# QTPyNoisyBoi.net
KiCad netlist of a schematic drawn in EAGLE
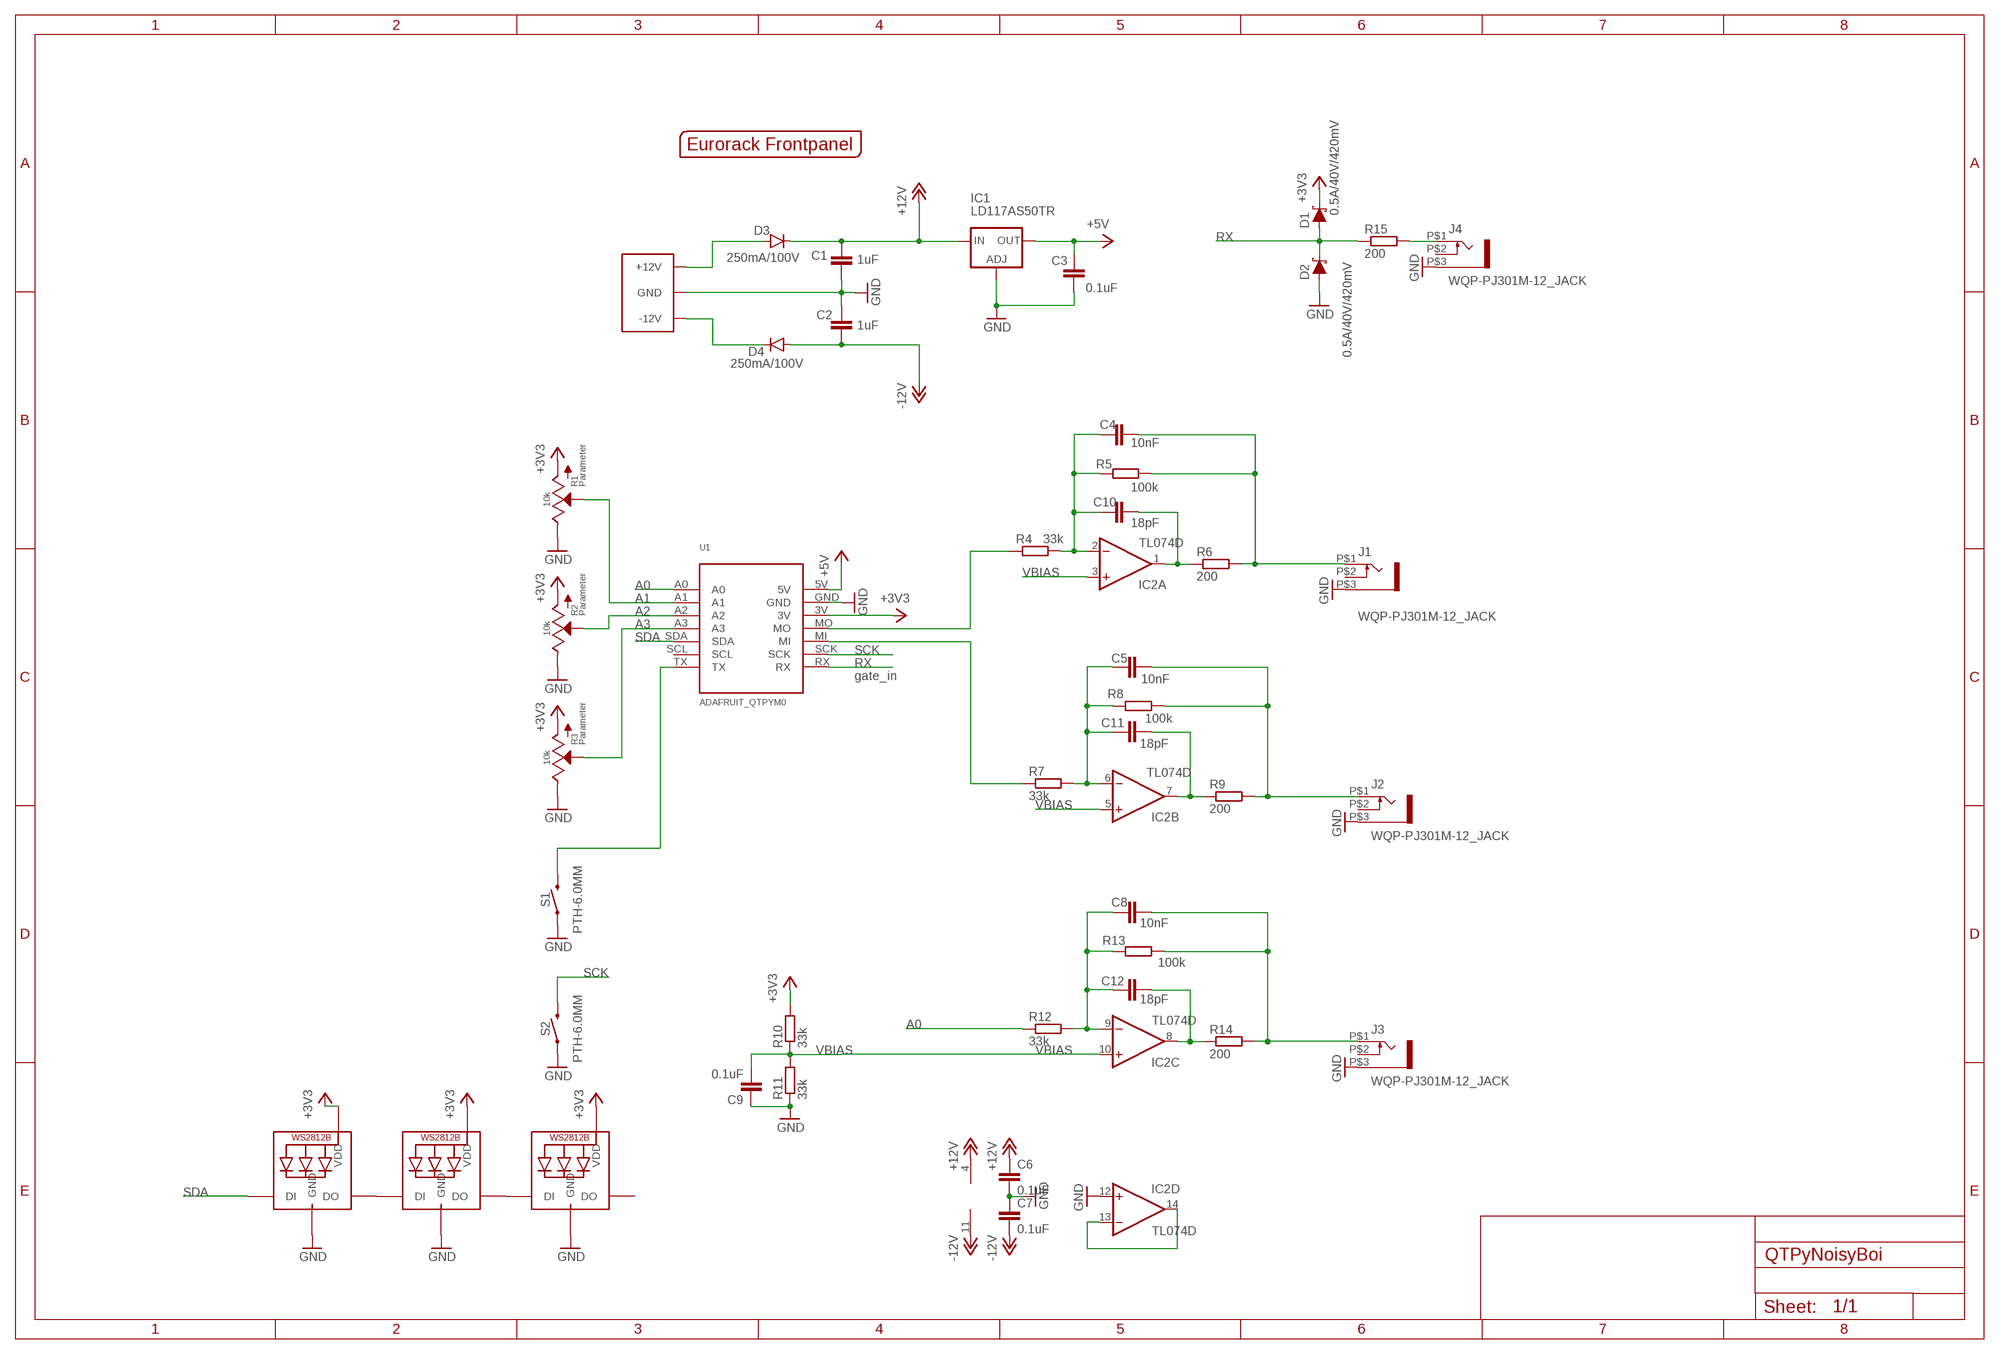
[diagram p0: schematic, sheet 1]

(export (version "E")
  (design (tool "Eeschema 10.0.6"))
  (components
    (comp (ref "C1")
      (value "1uF")
      (footprint "eagle-import:C0805")
      (libsource (lib "eagle-import") (part "C-EUC0805"))
    )
    (comp (ref "C2")
      (value "1uF")
      (footprint "eagle-import:C0805")
      (libsource (lib "eagle-import") (part "C-EUC0805"))
    )
    (comp (ref "C3")
      (value "0.1uF")
      (footprint "eagle-import:C0805")
      (libsource (lib "eagle-import") (part "C-EUC0805"))
    )
    (comp (ref "C4")
      (value "10nF")
      (footprint "eagle-import:C0805")
      (libsource (lib "eagle-import") (part "C-EUC0805"))
    )
    (comp (ref "C5")
      (value "10nF")
      (footprint "eagle-import:C0805")
      (libsource (lib "eagle-import") (part "C-EUC0805"))
    )
    (comp (ref "C6")
      (value "0.1uF")
      (footprint "eagle-import:C0805")
      (libsource (lib "eagle-import") (part "C-EUC0805"))
    )
    (comp (ref "C7")
      (value "0.1uF")
      (footprint "eagle-import:C0805")
      (libsource (lib "eagle-import") (part "C-EUC0805"))
    )
    (comp (ref "C8")
      (value "10nF")
      (footprint "eagle-import:C0805")
      (libsource (lib "eagle-import") (part "C-EUC0805"))
    )
    (comp (ref "C9")
      (value "0.1uF")
      (footprint "eagle-import:C0805")
      (libsource (lib "eagle-import") (part "C-EUC0805"))
    )
    (comp (ref "C10")
      (value "18pF")
      (footprint "eagle-import:C0805")
      (libsource (lib "eagle-import") (part "C-EUC0805"))
    )
    (comp (ref "C11")
      (value "18pF")
      (footprint "eagle-import:C0805")
      (libsource (lib "eagle-import") (part "C-EUC0805"))
    )
    (comp (ref "C12")
      (value "18pF")
      (footprint "eagle-import:C0805")
      (libsource (lib "eagle-import") (part "C-EUC0805"))
    )
    (comp (ref "D1")
      (value "0.5A/40V/420mV")
      (footprint "eagle-import:SOD-323")
      (libsource (lib "eagle-import") (part "DIODE-SCHOTTKY-PMEG4005EJ"))
    )
    (comp (ref "D2")
      (value "0.5A/40V/420mV")
      (footprint "eagle-import:SOD-323")
      (libsource (lib "eagle-import") (part "DIODE-SCHOTTKY-PMEG4005EJ"))
    )
    (comp (ref "D3")
      (value "250mA/100V")
      (footprint "eagle-import:SOD-323")
      (libsource (lib "eagle-import") (part "DIODEBAS16"))
    )
    (comp (ref "D4")
      (value "250mA/100V")
      (footprint "eagle-import:SOD-323")
      (libsource (lib "eagle-import") (part "DIODEBAS16"))
    )
    (comp (ref "DIM1")
      (value "EURO_POWER_LOCKSKINNY")
      (footprint "eagle-import:EURO_POWER_HEADER")
      (libsource (lib "eagle-import") (part "EURO_POWER_LOCKSKINNY"))
    )
    (comp (ref "IC1")
      (value "LD117AS50TR")
      (footprint "eagle-import:SOT223")
      (libsource (lib "eagle-import") (part "LD117A?S50TR"))
    )
    (comp (ref "IC2")
      (value "TL074D")
      (footprint "eagle-import:SO14")
      (libsource (lib "eagle-import") (part "TL074D"))
    )
    (comp (ref "J1")
      (value "WQP-PJ301M-12_JACK")
      (footprint "eagle-import:WQP-PJ301M-12_JACK")
      (libsource (lib "eagle-import") (part "WQP-PJ301M-12_JACK"))
    )
    (comp (ref "J2")
      (value "WQP-PJ301M-12_JACK")
      (footprint "eagle-import:WQP-PJ301M-12_JACK")
      (libsource (lib "eagle-import") (part "WQP-PJ301M-12_JACK"))
    )
    (comp (ref "J3")
      (value "WQP-PJ301M-12_JACK")
      (footprint "eagle-import:WQP-PJ301M-12_JACK")
      (libsource (lib "eagle-import") (part "WQP-PJ301M-12_JACK"))
    )
    (comp (ref "J4")
      (value "WQP-PJ301M-12_JACK")
      (footprint "eagle-import:WQP-PJ301M-12_JACK")
      (libsource (lib "eagle-import") (part "WQP-PJ301M-12_JACK"))
    )
    (comp (ref "LED1")
      (value "WS2812B5050")
      (footprint "eagle-import:WS2812B")
      (libsource (lib "eagle-import") (part "WS2812B5050"))
    )
    (comp (ref "LED2")
      (value "WS2812B5050")
      (footprint "eagle-import:WS2812B")
      (libsource (lib "eagle-import") (part "WS2812B5050"))
    )
    (comp (ref "LED3")
      (value "WS2812B5050")
      (footprint "eagle-import:WS2812B")
      (libsource (lib "eagle-import") (part "WS2812B5050"))
    )
    (comp (ref "R1")
      (value "10k")
      (footprint "eagle-import:OG-POTS_ALPS_POT_VERTICAL")
      (fields (field (name "DESC") "Parameter"))
      (libsource (lib "eagle-import") (part "POTZEPHPOT"))
    )
    (comp (ref "R2")
      (value "10k")
      (footprint "eagle-import:OG-POTS_ALPS_POT_VERTICAL")
      (fields (field (name "DESC") "Parameter"))
      (libsource (lib "eagle-import") (part "POTZEPHPOT"))
    )
    (comp (ref "R3")
      (value "10k")
      (footprint "eagle-import:OG-POTS_ALPS_POT_VERTICAL")
      (fields (field (name "DESC") "Parameter"))
      (libsource (lib "eagle-import") (part "POTZEPHPOT"))
    )
    (comp (ref "R4")
      (value "33k")
      (footprint "eagle-import:R0805")
      (libsource (lib "eagle-import") (part "R-EU_R0805"))
    )
    (comp (ref "R5")
      (value "100k")
      (footprint "eagle-import:R0805")
      (libsource (lib "eagle-import") (part "R-EU_R0805"))
    )
    (comp (ref "R6")
      (value "200")
      (footprint "eagle-import:R0805")
      (libsource (lib "eagle-import") (part "R-EU_R0805"))
    )
    (comp (ref "R7")
      (value "33k")
      (footprint "eagle-import:R0805")
      (libsource (lib "eagle-import") (part "R-EU_R0805"))
    )
    (comp (ref "R8")
      (value "100k")
      (footprint "eagle-import:R0805")
      (libsource (lib "eagle-import") (part "R-EU_R0805"))
    )
    (comp (ref "R9")
      (value "200")
      (footprint "eagle-import:R0805")
      (libsource (lib "eagle-import") (part "R-EU_R0805"))
    )
    (comp (ref "R10")
      (value "33k")
      (footprint "eagle-import:R0805")
      (libsource (lib "eagle-import") (part "R-EU_R0805"))
    )
    (comp (ref "R11")
      (value "33k")
      (footprint "eagle-import:R0805")
      (libsource (lib "eagle-import") (part "R-EU_R0805"))
    )
    (comp (ref "R12")
      (value "33k")
      (footprint "eagle-import:R0805")
      (libsource (lib "eagle-import") (part "R-EU_R0805"))
    )
    (comp (ref "R13")
      (value "100k")
      (footprint "eagle-import:R0805")
      (libsource (lib "eagle-import") (part "R-EU_R0805"))
    )
    (comp (ref "R14")
      (value "200")
      (footprint "eagle-import:R0805")
      (libsource (lib "eagle-import") (part "R-EU_R0805"))
    )
    (comp (ref "R15")
      (value "200")
      (footprint "eagle-import:R0805")
      (libsource (lib "eagle-import") (part "R-EU_R0805"))
    )
    (comp (ref "S1")
      (value "PTH-6.0MM")
      (footprint "eagle-import:TACTILE_SWITCH_PTH_6.0MM")
      (libsource (lib "eagle-import") (part "MOMENTARY-SWITCH-SPST-PTH-6.0MM"))
    )
    (comp (ref "S2")
      (value "PTH-6.0MM")
      (footprint "eagle-import:TACTILE_SWITCH_PTH_6.0MM")
      (libsource (lib "eagle-import") (part "MOMENTARY-SWITCH-SPST-PTH-6.0MM"))
    )
    (comp (ref "U$1")
      (value "EURORACK_PANEL6HP")
      (footprint "eagle-import:EURORACK6HPPANEL")
      (libsource (lib "eagle-import") (part "EURORACK_PANEL6HP"))
    )
    (comp (ref "U1")
      (value "ADAFRUIT_QTPYM0")
      (footprint "eagle-import:ADAFRUIT_QTPY_M0")
      (libsource (lib "eagle-import") (part "ADAFRUIT_QTPYM0"))
    )
  )
  (nets
    (net (code "1") (name "+3V3") (class "Default")
      (node (ref "D1") (pin "C") (pinfunction "C_C") (pintype "passive"))
      (node (ref "LED1") (pin "1-VDD") (pinfunction "VDD_1-VDD") (pintype "power_in"))
      (node (ref "LED2") (pin "1-VDD") (pinfunction "VDD_1-VDD") (pintype "power_in"))
      (node (ref "LED3") (pin "1-VDD") (pinfunction "VDD_1-VDD") (pintype "power_in"))
      (node (ref "R1") (pin "P$3") (pinfunction "A_P$3") (pintype "passive"))
      (node (ref "R10") (pin "2") (pinfunction "2_2") (pintype "passive"))
      (node (ref "R2") (pin "P$3") (pinfunction "A_P$3") (pintype "passive"))
      (node (ref "R3") (pin "P$3") (pinfunction "A_P$3") (pintype "passive"))
      (node (ref "U1") (pin "3V") (pinfunction "3V_3V") (pintype "bidirectional"))
    )
    (net (code "2") (name "+5V") (class "Default")
      (node (ref "C3") (pin "2") (pinfunction "2_2") (pintype "passive"))
      (node (ref "IC1") (pin "4") (pinfunction "OUT_4") (pintype "passive"))
      (node (ref "U1") (pin "5V") (pinfunction "5V_5V") (pintype "bidirectional"))
    )
    (net (code "3") (name "+12V") (class "Default")
      (node (ref "C1") (pin "2") (pinfunction "2_2") (pintype "passive"))
      (node (ref "C6") (pin "1") (pinfunction "1_1") (pintype "passive"))
      (node (ref "D3") (pin "C") (pinfunction "C_C") (pintype "passive"))
      (node (ref "IC1") (pin "3") (pinfunction "IN_3") (pintype "input"))
      (node (ref "IC2") (pin "4") (pinfunction "V+_4") (pintype "power_in"))
    )
    (net (code "4") (name "-12V") (class "Default")
      (node (ref "C2") (pin "1") (pinfunction "1_1") (pintype "passive"))
      (node (ref "C7") (pin "2") (pinfunction "2_2") (pintype "passive"))
      (node (ref "D4") (pin "A") (pinfunction "A_A") (pintype "passive"))
      (node (ref "IC2") (pin "11") (pinfunction "V-_11") (pintype "power_in"))
    )
    (net (code "5") (name "/A0") (class "Default")
      (node (ref "R12") (pin "1") (pinfunction "1_1") (pintype "passive"))
      (node (ref "U1") (pin "A0") (pinfunction "A0_A0") (pintype "bidirectional"))
    )
    (net (code "6") (name "/A1") (class "Default")
      (node (ref "R1") (pin "P$2") (pinfunction "S_P$2") (pintype "passive"))
      (node (ref "U1") (pin "A1") (pinfunction "A1_A1") (pintype "bidirectional"))
    )
    (net (code "7") (name "/A2") (class "Default")
      (node (ref "R2") (pin "P$2") (pinfunction "S_P$2") (pintype "passive"))
      (node (ref "U1") (pin "A2") (pinfunction "A2_A2") (pintype "bidirectional"))
    )
    (net (code "8") (name "/A3") (class "Default")
      (node (ref "R3") (pin "P$2") (pinfunction "S_P$2") (pintype "passive"))
      (node (ref "U1") (pin "A3") (pinfunction "A3_A3") (pintype "bidirectional"))
    )
    (net (code "9") (name "/RX") (class "Default")
      (node (ref "D1") (pin "A") (pinfunction "A_A") (pintype "passive"))
      (node (ref "D2") (pin "C") (pinfunction "C_C") (pintype "passive"))
      (node (ref "R15") (pin "1") (pinfunction "1_1") (pintype "passive"))
      (node (ref "U1") (pin "RX") (pinfunction "RX_RX") (pintype "bidirectional"))
    )
    (net (code "10") (name "/SCK") (class "Default")
      (node (ref "S2") (pin "3") (pinfunction "2_3") (pintype "passive"))
      (node (ref "U1") (pin "SCK") (pinfunction "SCK_SCK") (pintype "bidirectional"))
    )
    (net (code "11") (name "/SDA") (class "Default")
      (node (ref "LED1") (pin "4-DIN") (pinfunction "DI_4-DIN") (pintype "input"))
      (node (ref "U1") (pin "SDA") (pinfunction "SDA_SDA") (pintype "bidirectional"))
    )
    (net (code "12") (name "/VBIAS") (class "Default")
      (node (ref "C9") (pin "2") (pinfunction "2_2") (pintype "passive"))
      (node (ref "IC2") (pin "10") (pinfunction "+IN_10") (pintype "input"))
      (node (ref "IC2") (pin "3") (pinfunction "+IN_3") (pintype "input"))
      (node (ref "IC2") (pin "5") (pinfunction "+IN_5") (pintype "input"))
      (node (ref "R10") (pin "1") (pinfunction "1_1") (pintype "passive"))
      (node (ref "R11") (pin "2") (pinfunction "2_2") (pintype "passive"))
    )
    (net (code "13") (name "GND") (class "Default")
      (node (ref "C1") (pin "1") (pinfunction "1_1") (pintype "passive"))
      (node (ref "C2") (pin "2") (pinfunction "2_2") (pintype "passive"))
      (node (ref "C3") (pin "1") (pinfunction "1_1") (pintype "passive"))
      (node (ref "C6") (pin "2") (pinfunction "2_2") (pintype "passive"))
      (node (ref "C7") (pin "1") (pinfunction "1_1") (pintype "passive"))
      (node (ref "C9") (pin "1") (pinfunction "1_1") (pintype "passive"))
      (node (ref "D2") (pin "A") (pinfunction "A_A") (pintype "passive"))
      (node (ref "DIM1") (pin "3") (pinfunction "GND_3") (pintype "bidirectional"))
      (node (ref "DIM1") (pin "4") (pinfunction "GND_4") (pintype "bidirectional"))
      (node (ref "DIM1") (pin "5") (pinfunction "GND_5") (pintype "bidirectional"))
      (node (ref "DIM1") (pin "6") (pinfunction "GND_6") (pintype "bidirectional"))
      (node (ref "DIM1") (pin "7") (pinfunction "GND_7") (pintype "bidirectional"))
      (node (ref "DIM1") (pin "8") (pinfunction "GND_8") (pintype "bidirectional"))
      (node (ref "IC1") (pin "1") (pinfunction "ADJ_1") (pintype "input"))
      (node (ref "IC2") (pin "12") (pinfunction "+IN_12") (pintype "input"))
      (node (ref "J1") (pin "P$3") (pinfunction "1_P$3") (pintype "passive"))
      (node (ref "J2") (pin "P$3") (pinfunction "1_P$3") (pintype "passive"))
      (node (ref "J3") (pin "P$3") (pinfunction "1_P$3") (pintype "passive"))
      (node (ref "J4") (pin "P$3") (pinfunction "1_P$3") (pintype "passive"))
      (node (ref "LED1") (pin "3-GND") (pinfunction "GND_3-GND") (pintype "power_in"))
      (node (ref "LED2") (pin "3-GND") (pinfunction "GND_3-GND") (pintype "power_in"))
      (node (ref "LED3") (pin "3-GND") (pinfunction "GND_3-GND") (pintype "power_in"))
      (node (ref "R1") (pin "P$1") (pinfunction "E_P$1") (pintype "passive"))
      (node (ref "R11") (pin "1") (pinfunction "1_1") (pintype "passive"))
      (node (ref "R2") (pin "P$1") (pinfunction "E_P$1") (pintype "passive"))
      (node (ref "R3") (pin "P$1") (pinfunction "E_P$1") (pintype "passive"))
      (node (ref "S1") (pin "1") (pinfunction "1_1") (pintype "passive"))
      (node (ref "S2") (pin "1") (pinfunction "1_1") (pintype "passive"))
      (node (ref "U1") (pin "GND") (pinfunction "GND_GND") (pintype "bidirectional"))
    )
    (net (code "14") (name "Net-(D3-PadA)") (class "Default")
      (node (ref "D3") (pin "A") (pinfunction "A_A") (pintype "passive"))
      (node (ref "DIM1") (pin "10") (pinfunction "+12V_10") (pintype "bidirectional"))
      (node (ref "DIM1") (pin "9") (pinfunction "+12V_9") (pintype "bidirectional"))
    )
    (net (code "15") (name "Net-(D4-PadC)") (class "Default")
      (node (ref "D4") (pin "C") (pinfunction "C_C") (pintype "passive"))
      (node (ref "DIM1") (pin "1") (pinfunction "-12V_1") (pintype "bidirectional"))
      (node (ref "DIM1") (pin "2") (pinfunction "-12V_2") (pintype "bidirectional"))
    )
    (net (code "16") (name "Net-(IC2A--IN)") (class "Default")
      (node (ref "C10") (pin "1") (pinfunction "1_1") (pintype "passive"))
      (node (ref "C4") (pin "1") (pinfunction "1_1") (pintype "passive"))
      (node (ref "IC2") (pin "2") (pinfunction "-IN_2") (pintype "input"))
      (node (ref "R4") (pin "2") (pinfunction "2_2") (pintype "passive"))
      (node (ref "R5") (pin "1") (pinfunction "1_1") (pintype "passive"))
    )
    (net (code "17") (name "Net-(IC2A-OUT)") (class "Default")
      (node (ref "C10") (pin "2") (pinfunction "2_2") (pintype "passive"))
      (node (ref "IC2") (pin "1") (pinfunction "OUT_1") (pintype "output"))
      (node (ref "R6") (pin "1") (pinfunction "1_1") (pintype "passive"))
    )
    (net (code "18") (name "Net-(IC2B--IN)") (class "Default")
      (node (ref "C11") (pin "1") (pinfunction "1_1") (pintype "passive"))
      (node (ref "C5") (pin "1") (pinfunction "1_1") (pintype "passive"))
      (node (ref "IC2") (pin "6") (pinfunction "-IN_6") (pintype "input"))
      (node (ref "R7") (pin "2") (pinfunction "2_2") (pintype "passive"))
      (node (ref "R8") (pin "1") (pinfunction "1_1") (pintype "passive"))
    )
    (net (code "19") (name "Net-(IC2B-OUT)") (class "Default")
      (node (ref "C11") (pin "2") (pinfunction "2_2") (pintype "passive"))
      (node (ref "IC2") (pin "7") (pinfunction "OUT_7") (pintype "output"))
      (node (ref "R9") (pin "1") (pinfunction "1_1") (pintype "passive"))
    )
    (net (code "20") (name "Net-(IC2C--IN)") (class "Default")
      (node (ref "C12") (pin "1") (pinfunction "1_1") (pintype "passive"))
      (node (ref "C8") (pin "1") (pinfunction "1_1") (pintype "passive"))
      (node (ref "IC2") (pin "9") (pinfunction "-IN_9") (pintype "input"))
      (node (ref "R12") (pin "2") (pinfunction "2_2") (pintype "passive"))
      (node (ref "R13") (pin "1") (pinfunction "1_1") (pintype "passive"))
    )
    (net (code "21") (name "Net-(IC2C-OUT)") (class "Default")
      (node (ref "C12") (pin "2") (pinfunction "2_2") (pintype "passive"))
      (node (ref "IC2") (pin "8") (pinfunction "OUT_8") (pintype "output"))
      (node (ref "R14") (pin "1") (pinfunction "1_1") (pintype "passive"))
    )
    (net (code "22") (name "Net-(IC2D--IN)") (class "Default")
      (node (ref "IC2") (pin "13") (pinfunction "-IN_13") (pintype "input"))
      (node (ref "IC2") (pin "14") (pinfunction "OUT_14") (pintype "output"))
    )
    (net (code "23") (name "Net-(J1-2)") (class "Default")
      (node (ref "C4") (pin "2") (pinfunction "2_2") (pintype "passive"))
      (node (ref "J1") (pin "P$1") (pinfunction "2_P$1") (pintype "passive"))
      (node (ref "R5") (pin "2") (pinfunction "2_2") (pintype "passive"))
      (node (ref "R6") (pin "2") (pinfunction "2_2") (pintype "passive"))
    )
    (net (code "24") (name "Net-(J2-2)") (class "Default")
      (node (ref "C5") (pin "2") (pinfunction "2_2") (pintype "passive"))
      (node (ref "J2") (pin "P$1") (pinfunction "2_P$1") (pintype "passive"))
      (node (ref "R8") (pin "2") (pinfunction "2_2") (pintype "passive"))
      (node (ref "R9") (pin "2") (pinfunction "2_2") (pintype "passive"))
    )
    (net (code "25") (name "Net-(J3-2)") (class "Default")
      (node (ref "C8") (pin "2") (pinfunction "2_2") (pintype "passive"))
      (node (ref "J3") (pin "P$1") (pinfunction "2_P$1") (pintype "passive"))
      (node (ref "R13") (pin "2") (pinfunction "2_2") (pintype "passive"))
      (node (ref "R14") (pin "2") (pinfunction "2_2") (pintype "passive"))
    )
    (net (code "26") (name "Net-(J4-2)") (class "Default")
      (node (ref "J4") (pin "P$1") (pinfunction "2_P$1") (pintype "passive"))
      (node (ref "R15") (pin "2") (pinfunction "2_2") (pintype "passive"))
    )
    (net (code "27") (name "Net-(LED1-DO)") (class "Default")
      (node (ref "LED1") (pin "2-DOUT") (pinfunction "DO_2-DOUT") (pintype "output"))
      (node (ref "LED2") (pin "4-DIN") (pinfunction "DI_4-DIN") (pintype "input"))
    )
    (net (code "28") (name "Net-(LED2-DO)") (class "Default")
      (node (ref "LED2") (pin "2-DOUT") (pinfunction "DO_2-DOUT") (pintype "output"))
      (node (ref "LED3") (pin "4-DIN") (pinfunction "DI_4-DIN") (pintype "input"))
    )
    (net (code "29") (name "Net-(R4-Pad1)") (class "Default")
      (node (ref "R4") (pin "1") (pinfunction "1_1") (pintype "passive"))
      (node (ref "U1") (pin "MO") (pinfunction "MO_MO") (pintype "bidirectional"))
    )
    (net (code "30") (name "Net-(R7-Pad1)") (class "Default")
      (node (ref "R7") (pin "1") (pinfunction "1_1") (pintype "passive"))
      (node (ref "U1") (pin "MI") (pinfunction "MI_MI") (pintype "bidirectional"))
    )
    (net (code "31") (name "Net-(S1-2)") (class "Default")
      (node (ref "S1") (pin "3") (pinfunction "2_3") (pintype "passive"))
      (node (ref "U1") (pin "TX") (pinfunction "TX_TX") (pintype "bidirectional"))
    )
    (net (code "32") (name "unconnected-(J1-3-PadP$2)") (class "Default")
      (node (ref "J1") (pin "P$2") (pinfunction "3_P$2") (pintype "passive"))
    )
    (net (code "33") (name "unconnected-(J2-3-PadP$2)") (class "Default")
      (node (ref "J2") (pin "P$2") (pinfunction "3_P$2") (pintype "passive"))
    )
    (net (code "34") (name "unconnected-(J3-3-PadP$2)") (class "Default")
      (node (ref "J3") (pin "P$2") (pinfunction "3_P$2") (pintype "passive"))
    )
    (net (code "35") (name "unconnected-(J4-3-PadP$2)") (class "Default")
      (node (ref "J4") (pin "P$2") (pinfunction "3_P$2") (pintype "passive"))
    )
    (net (code "36") (name "unconnected-(LED3-DO-Pad2-DOUT)") (class "Default")
      (node (ref "LED3") (pin "2-DOUT") (pinfunction "DO_2-DOUT") (pintype "output"))
    )
    (net (code "37") (name "unconnected-(U1-PadSCL)") (class "Default")
      (node (ref "U1") (pin "SCL") (pinfunction "SCL_SCL") (pintype "bidirectional"))
    )
  )
)
